# ethernet.net
KiCad netlist of a schematic drawn in EAGLE
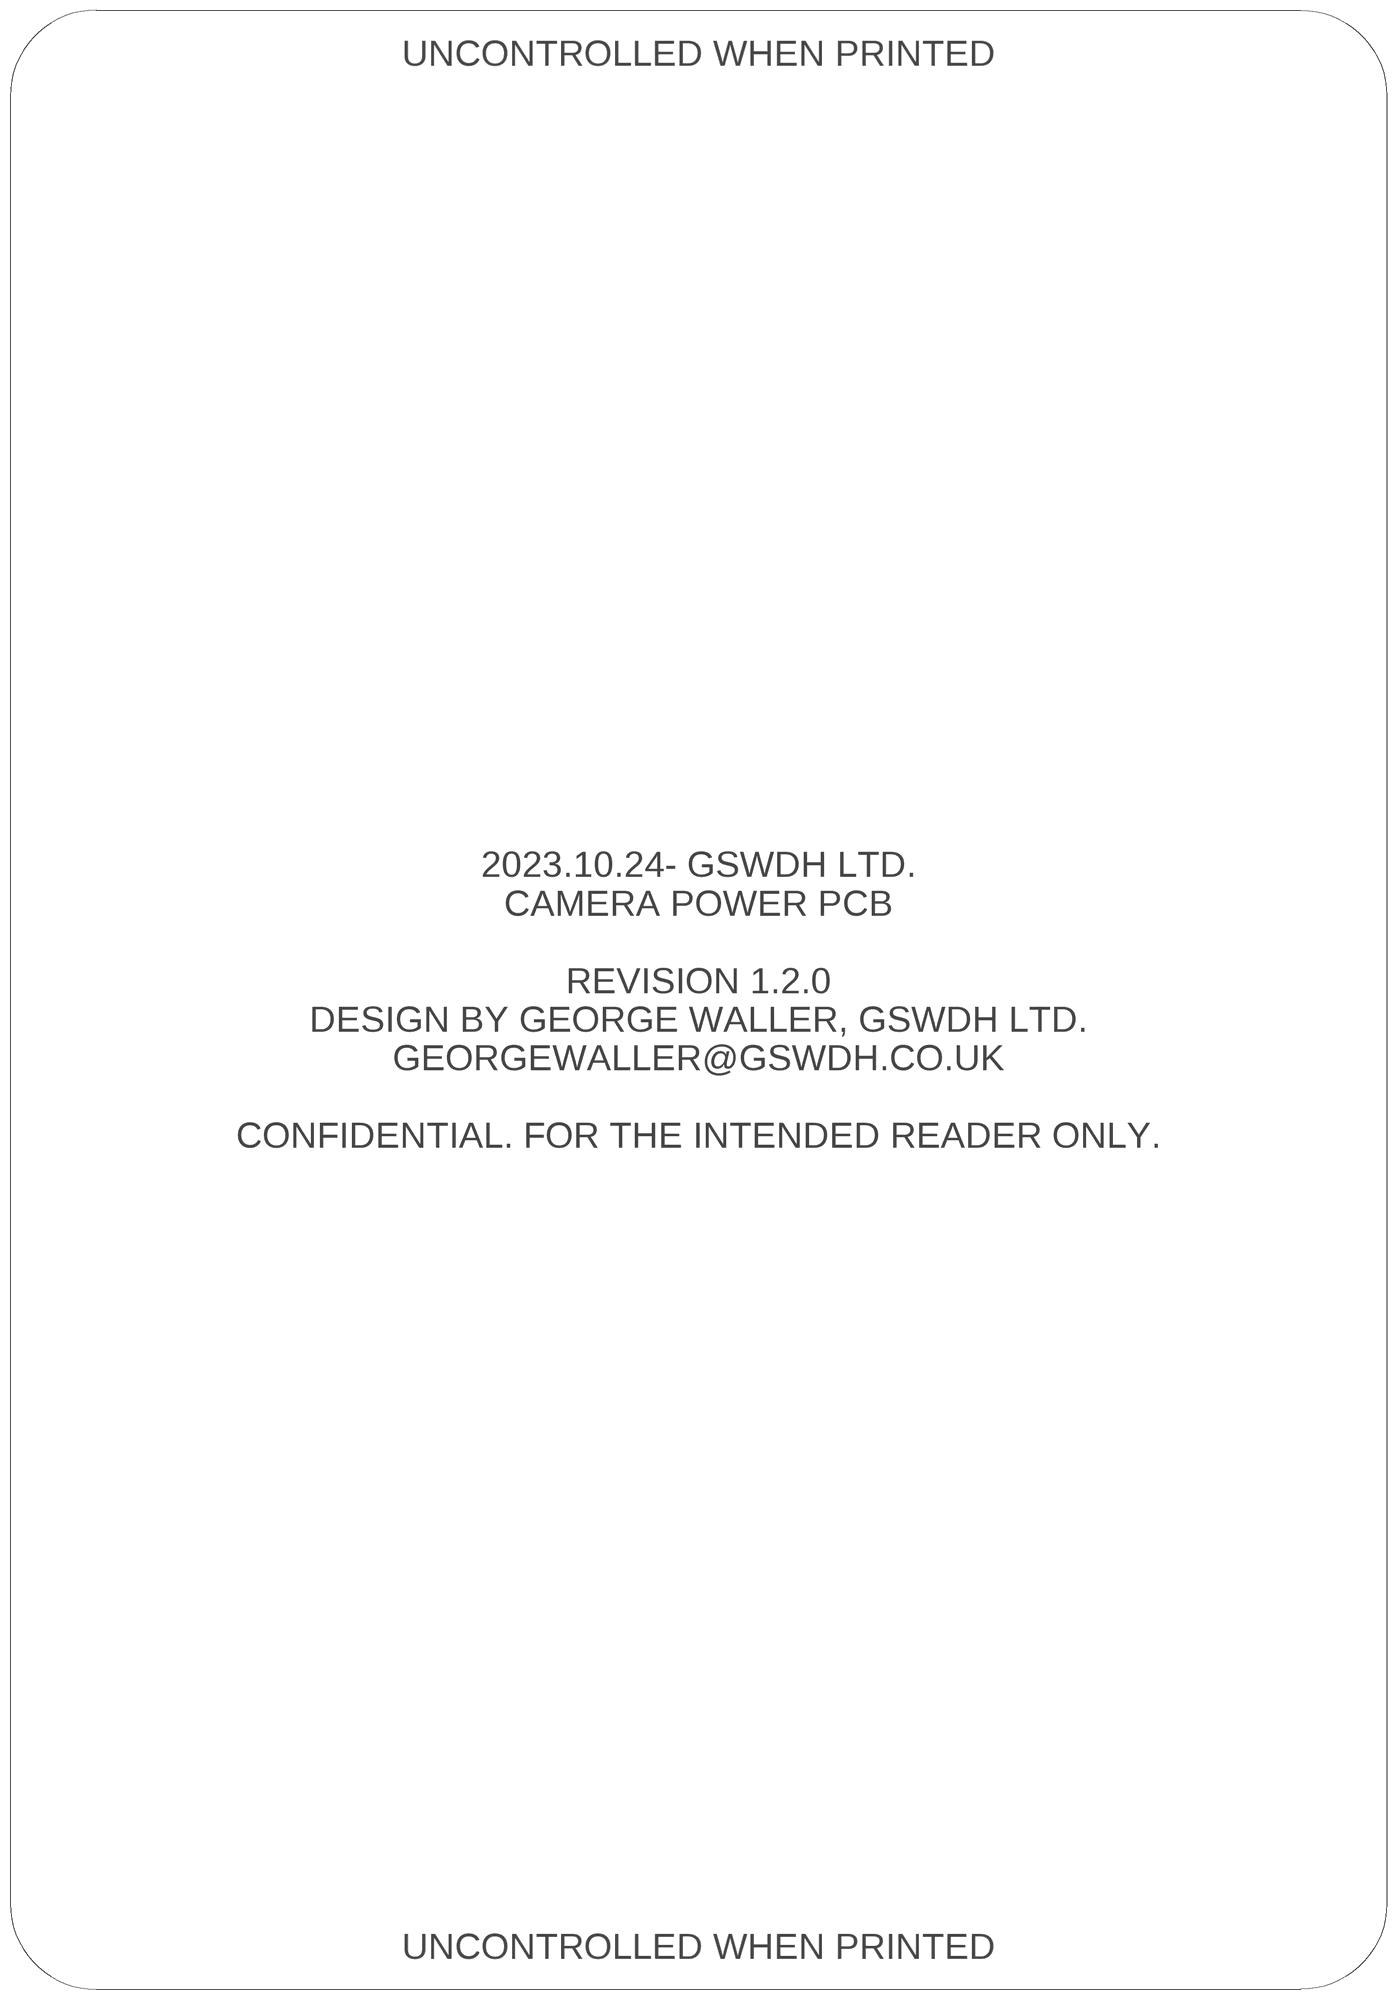
[diagram p0: schematic, sheet 1]
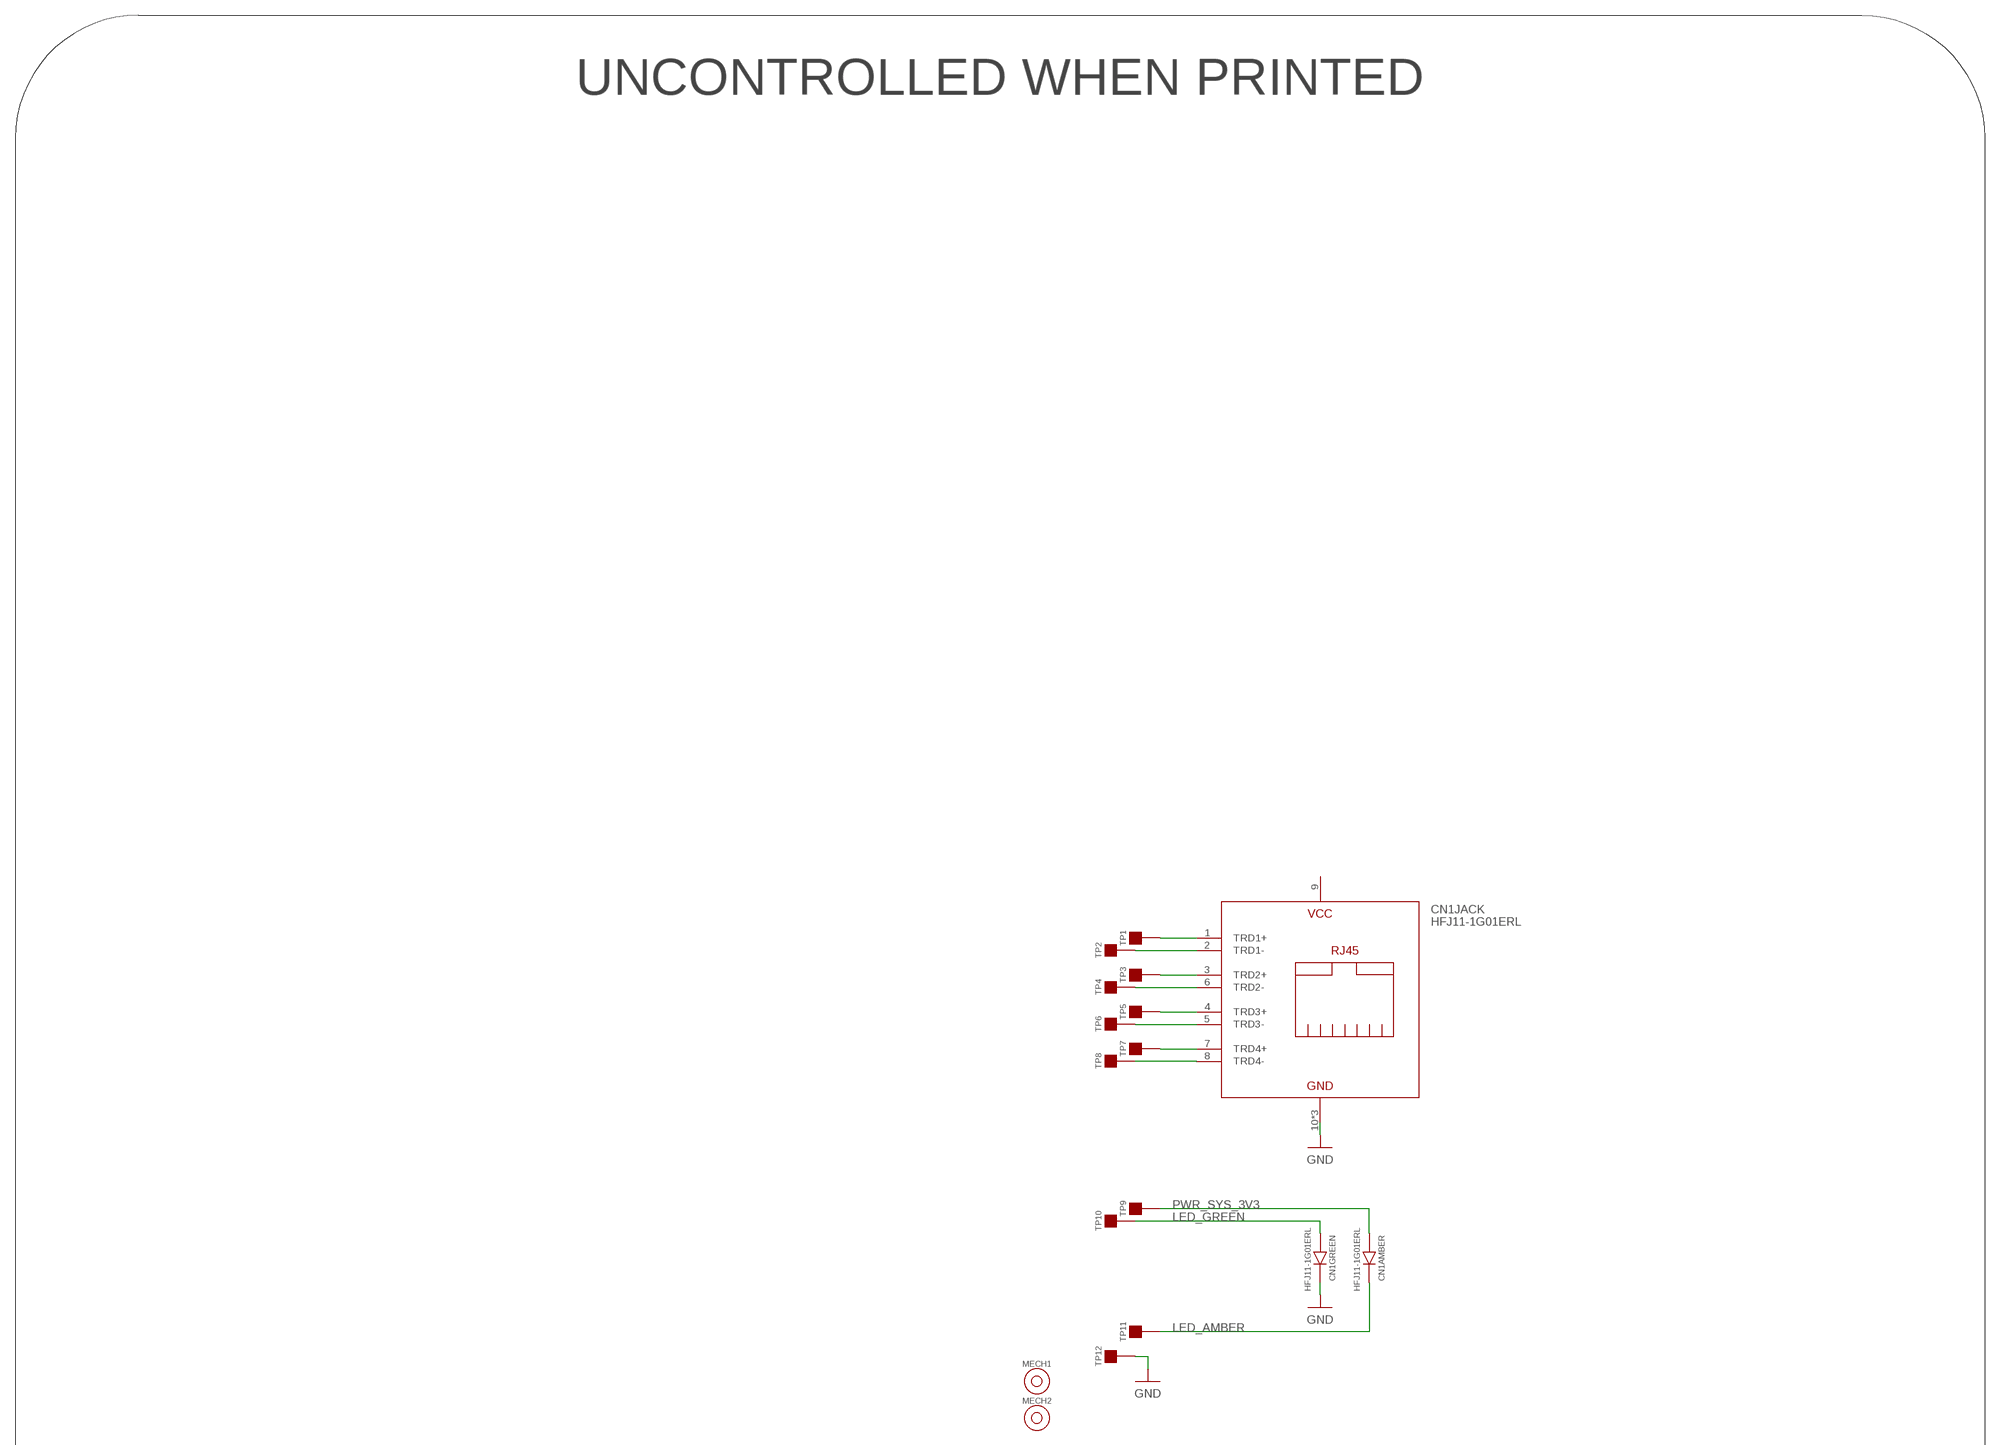
[diagram p1: schematic, sheet 2, part 1 of 2]
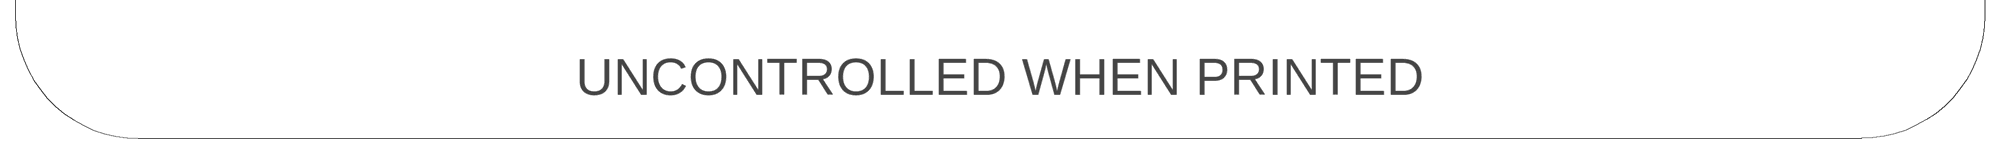
[diagram p2: schematic, sheet 2, part 2 of 2]

(export (version "E")
  (design (tool "Eeschema 10.0.6"))
  (components
    (comp (ref "CN1")
      (value "HFJ11-1G01ERL")
      (footprint "eagle-import:HFJ11-1G")
      (libsource (lib "eagle-import") (part "HFJ11-1G01ERL"))
    )
    (comp (ref "MECH1")
      (value "6mm x 3mm")
      (footprint "eagle-import:MOUNTHOLE_6X3")
      (libsource (lib "eagle-import") (part "MOUNTHOLE"))
    )
    (comp (ref "MECH2")
      (value "6mm x 3mm")
      (footprint "eagle-import:MOUNTHOLE_6X3")
      (libsource (lib "eagle-import") (part "MOUNTHOLE"))
    )
    (comp (ref "TP1")
      (value "TEST_POINT_SQUARE")
      (footprint "eagle-import:OSPREY_HSS_PAD")
      (libsource (lib "eagle-import") (part "TEST_POINT_SQUARE"))
    )
    (comp (ref "TP2")
      (value "TEST_POINT_SQUARE")
      (footprint "eagle-import:OSPREY_HSS_PAD")
      (libsource (lib "eagle-import") (part "TEST_POINT_SQUARE"))
    )
    (comp (ref "TP3")
      (value "TEST_POINT_SQUARE")
      (footprint "eagle-import:OSPREY_HSS_PAD")
      (libsource (lib "eagle-import") (part "TEST_POINT_SQUARE"))
    )
    (comp (ref "TP4")
      (value "TEST_POINT_SQUARE")
      (footprint "eagle-import:OSPREY_HSS_PAD")
      (libsource (lib "eagle-import") (part "TEST_POINT_SQUARE"))
    )
    (comp (ref "TP5")
      (value "TEST_POINT_SQUARE")
      (footprint "eagle-import:OSPREY_HSS_PAD")
      (libsource (lib "eagle-import") (part "TEST_POINT_SQUARE"))
    )
    (comp (ref "TP6")
      (value "TEST_POINT_SQUARE")
      (footprint "eagle-import:OSPREY_HSS_PAD")
      (libsource (lib "eagle-import") (part "TEST_POINT_SQUARE"))
    )
    (comp (ref "TP7")
      (value "TEST_POINT_SQUARE")
      (footprint "eagle-import:OSPREY_HSS_PAD")
      (libsource (lib "eagle-import") (part "TEST_POINT_SQUARE"))
    )
    (comp (ref "TP8")
      (value "TEST_POINT_SQUARE")
      (footprint "eagle-import:OSPREY_HSS_PAD")
      (libsource (lib "eagle-import") (part "TEST_POINT_SQUARE"))
    )
    (comp (ref "TP9")
      (value "TEST_POINT_SQUARE")
      (footprint "eagle-import:OSPREY_HSS_PAD")
      (libsource (lib "eagle-import") (part "TEST_POINT_SQUARE"))
    )
    (comp (ref "TP10")
      (value "TEST_POINT_SQUARE")
      (footprint "eagle-import:OSPREY_HSS_PAD")
      (libsource (lib "eagle-import") (part "TEST_POINT_SQUARE"))
    )
    (comp (ref "TP11")
      (value "TEST_POINT_SQUARE")
      (footprint "eagle-import:OSPREY_HSS_PAD")
      (libsource (lib "eagle-import") (part "TEST_POINT_SQUARE"))
    )
    (comp (ref "TP12")
      (value "TEST_POINT_SQUARE")
      (footprint "eagle-import:OSPREY_HSS_PAD")
      (libsource (lib "eagle-import") (part "TEST_POINT_SQUARE"))
    )
  )
  (nets
    (net (code "1") (name "GND") (class "Default")
      (node (ref "CN1") (pin "10") (pinfunction "GND_10") (pintype "bidirectional"))
      (node (ref "CN1") (pin "12") (pinfunction "K_12") (pintype "bidirectional"))
      (node (ref "CN1") (pin "SH1") (pinfunction "GND_SH1") (pintype "bidirectional"))
      (node (ref "CN1") (pin "SH2") (pinfunction "GND_SH2") (pintype "bidirectional"))
      (node (ref "TP12") (pin "1") (pinfunction "P$1_1") (pintype "bidirectional"))
    )
    (net (code "2") (name "LED_AMBER") (class "Default")
      (node (ref "CN1") (pin "14") (pinfunction "K_14") (pintype "bidirectional"))
      (node (ref "TP11") (pin "1") (pinfunction "P$1_1") (pintype "bidirectional"))
    )
    (net (code "3") (name "LED_GREEN") (class "Default")
      (node (ref "CN1") (pin "11") (pinfunction "A_11") (pintype "bidirectional"))
      (node (ref "TP10") (pin "1") (pinfunction "P$1_1") (pintype "bidirectional"))
    )
    (net (code "4") (name "Net-(CN1C-TRD1+)") (class "Default")
      (node (ref "CN1") (pin "1") (pinfunction "TRD1+_1") (pintype "bidirectional"))
      (node (ref "TP1") (pin "1") (pinfunction "P$1_1") (pintype "bidirectional"))
    )
    (net (code "5") (name "Net-(CN1C-TRD1-)") (class "Default")
      (node (ref "CN1") (pin "2") (pinfunction "TRD1-_2") (pintype "bidirectional"))
      (node (ref "TP2") (pin "1") (pinfunction "P$1_1") (pintype "bidirectional"))
    )
    (net (code "6") (name "Net-(CN1C-TRD2+)") (class "Default")
      (node (ref "CN1") (pin "3") (pinfunction "TRD2+_3") (pintype "bidirectional"))
      (node (ref "TP3") (pin "1") (pinfunction "P$1_1") (pintype "bidirectional"))
    )
    (net (code "7") (name "Net-(CN1C-TRD2-)") (class "Default")
      (node (ref "CN1") (pin "6") (pinfunction "TRD2-_6") (pintype "bidirectional"))
      (node (ref "TP4") (pin "1") (pinfunction "P$1_1") (pintype "bidirectional"))
    )
    (net (code "8") (name "Net-(CN1C-TRD3+)") (class "Default")
      (node (ref "CN1") (pin "4") (pinfunction "TRD3+_4") (pintype "bidirectional"))
      (node (ref "TP5") (pin "1") (pinfunction "P$1_1") (pintype "bidirectional"))
    )
    (net (code "9") (name "Net-(CN1C-TRD3-)") (class "Default")
      (node (ref "CN1") (pin "5") (pinfunction "TRD3-_5") (pintype "bidirectional"))
      (node (ref "TP6") (pin "1") (pinfunction "P$1_1") (pintype "bidirectional"))
    )
    (net (code "10") (name "Net-(CN1C-TRD4+)") (class "Default")
      (node (ref "CN1") (pin "7") (pinfunction "TRD4+_7") (pintype "bidirectional"))
      (node (ref "TP7") (pin "1") (pinfunction "P$1_1") (pintype "bidirectional"))
    )
    (net (code "11") (name "Net-(CN1C-TRD4-)") (class "Default")
      (node (ref "CN1") (pin "8") (pinfunction "TRD4-_8") (pintype "bidirectional"))
      (node (ref "TP8") (pin "1") (pinfunction "P$1_1") (pintype "bidirectional"))
    )
    (net (code "12") (name "PWR_SYS_3V3") (class "Default")
      (node (ref "CN1") (pin "13") (pinfunction "A_13") (pintype "bidirectional"))
      (node (ref "TP9") (pin "1") (pinfunction "P$1_1") (pintype "bidirectional"))
    )
    (net (code "13") (name "unconnected-(CN1C-VCC-Pad9)") (class "Default")
      (node (ref "CN1") (pin "9") (pinfunction "VCC_9") (pintype "bidirectional"))
    )
  )
)
